# list_1.net
KiCad netlist of a schematic drawn in EAGLE
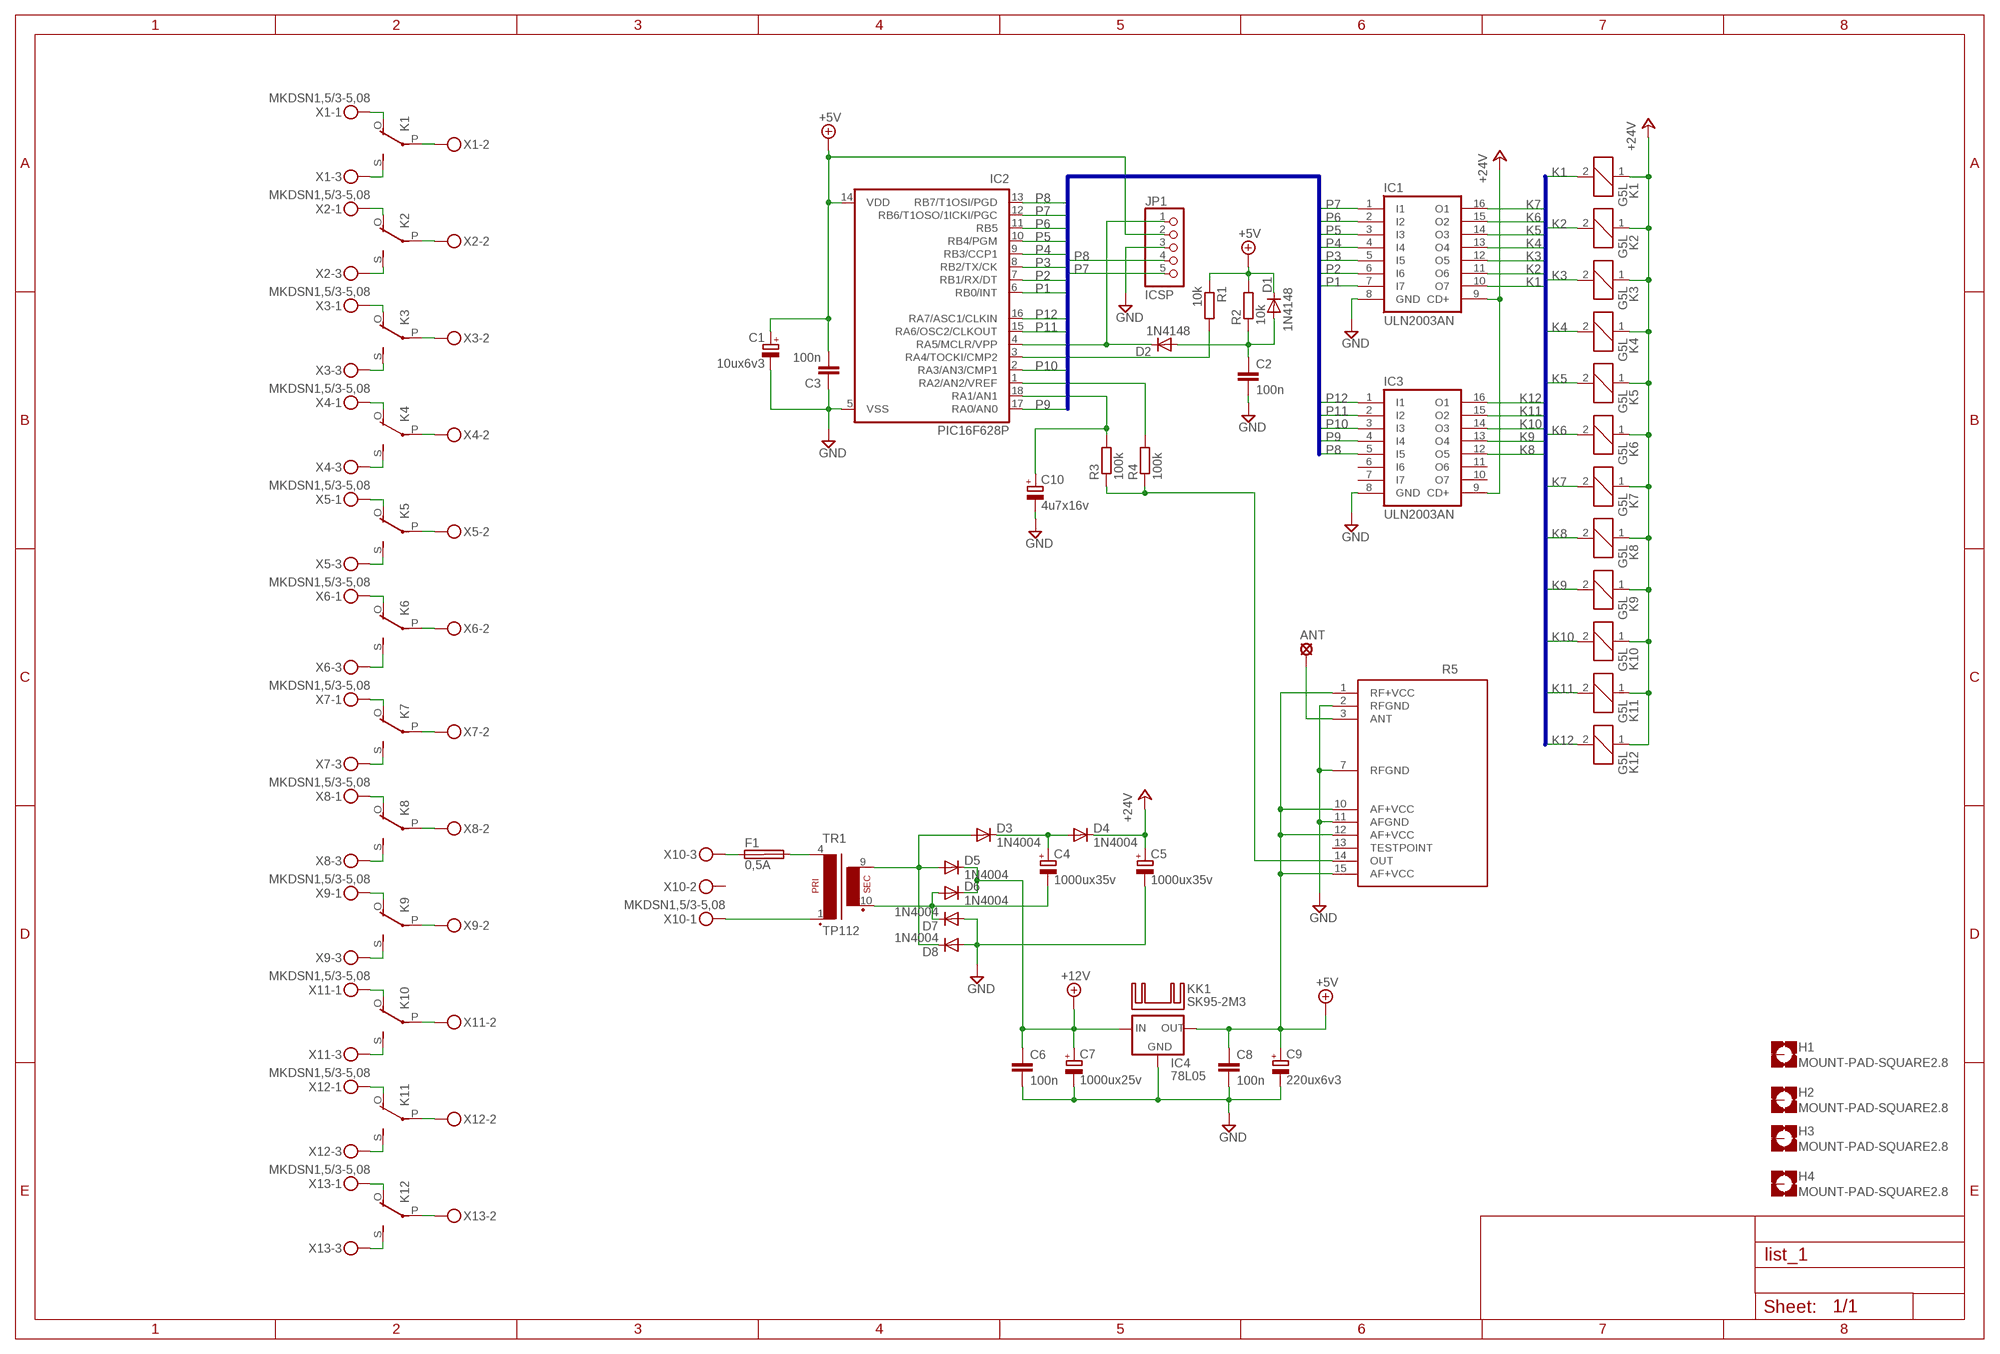
[diagram p0: schematic, sheet 1]

(export (version "E")
  (design (tool "Eeschema 10.0.6"))
  (components
    (comp (ref "ANT")
      (value "SE14")
      (footprint "eagle-import:SE14")
      (libsource (lib "eagle-import") (part "SE14"))
    )
    (comp (ref "C1")
      (value "10ux6v3")
      (footprint "eagle-import:E2,5-5")
      (libsource (lib "eagle-import") (part "CPOL-EUE2.5-5"))
    )
    (comp (ref "C2")
      (value "100n")
      (footprint "eagle-import:C050-025X075")
      (libsource (lib "eagle-import") (part "C-EU050-025X075"))
    )
    (comp (ref "C3")
      (value "100n")
      (footprint "eagle-import:C050-025X075")
      (libsource (lib "eagle-import") (part "C-EU050-025X075"))
    )
    (comp (ref "C4")
      (value "1000ux35v")
      (footprint "eagle-import:E3,5-8")
      (libsource (lib "eagle-import") (part "CPOL-EUE3.5-8"))
    )
    (comp (ref "C5")
      (value "1000ux35v")
      (footprint "eagle-import:E3,5-10")
      (libsource (lib "eagle-import") (part "CPOL-EUE3.5-10"))
    )
    (comp (ref "C6")
      (value "100n")
      (footprint "eagle-import:C050-025X075")
      (libsource (lib "eagle-import") (part "C-EU050-025X075"))
    )
    (comp (ref "C7")
      (value "1000ux25v")
      (footprint "eagle-import:E3,5-8")
      (libsource (lib "eagle-import") (part "CPOL-EUE3.5-8"))
    )
    (comp (ref "C8")
      (value "100n")
      (footprint "eagle-import:C050-025X075")
      (libsource (lib "eagle-import") (part "C-EU050-025X075"))
    )
    (comp (ref "C9")
      (value "220ux6v3")
      (footprint "eagle-import:E2,5-5")
      (libsource (lib "eagle-import") (part "CPOL-EUE2.5-5"))
    )
    (comp (ref "C10")
      (value "4u7x16v")
      (footprint "eagle-import:E2,5-5")
      (libsource (lib "eagle-import") (part "CPOL-EUE2.5-5"))
    )
    (comp (ref "D1")
      (value "1N4148")
      (footprint "eagle-import:DO35-10")
      (libsource (lib "eagle-import") (part "1N4148DO35-10"))
    )
    (comp (ref "D2")
      (value "1N4148")
      (footprint "eagle-import:DO35-10")
      (libsource (lib "eagle-import") (part "1N4148DO35-10"))
    )
    (comp (ref "D3")
      (value "1N4004")
      (footprint "eagle-import:DO41-10")
      (libsource (lib "eagle-import") (part "1N4004"))
    )
    (comp (ref "D4")
      (value "1N4004")
      (footprint "eagle-import:DO41-10")
      (libsource (lib "eagle-import") (part "1N4004"))
    )
    (comp (ref "D5")
      (value "1N4004")
      (footprint "eagle-import:DO41-10")
      (libsource (lib "eagle-import") (part "1N4004"))
    )
    (comp (ref "D6")
      (value "1N4004")
      (footprint "eagle-import:DO41-10")
      (libsource (lib "eagle-import") (part "1N4004"))
    )
    (comp (ref "D7")
      (value "1N4004")
      (footprint "eagle-import:DO41-10")
      (libsource (lib "eagle-import") (part "1N4004"))
    )
    (comp (ref "D8")
      (value "1N4004")
      (footprint "eagle-import:DO41-10")
      (libsource (lib "eagle-import") (part "1N4004"))
    )
    (comp (ref "F1")
      (value "0,5A")
      (footprint "eagle-import:SHK20L")
      (libsource (lib "eagle-import") (part "SHK20L"))
    )
    (comp (ref "H1")
      (value "MOUNT-PAD-SQUARE2.8")
      (footprint "eagle-import:2,8-PAD-SQUARE")
      (libsource (lib "eagle-import") (part "MOUNT-PAD-SQUARE2.8"))
    )
    (comp (ref "H2")
      (value "MOUNT-PAD-SQUARE2.8")
      (footprint "eagle-import:2,8-PAD-SQUARE")
      (libsource (lib "eagle-import") (part "MOUNT-PAD-SQUARE2.8"))
    )
    (comp (ref "H3")
      (value "MOUNT-PAD-SQUARE2.8")
      (footprint "eagle-import:2,8-PAD-SQUARE")
      (libsource (lib "eagle-import") (part "MOUNT-PAD-SQUARE2.8"))
    )
    (comp (ref "H4")
      (value "MOUNT-PAD-SQUARE2.8")
      (footprint "eagle-import:2,8-PAD-SQUARE")
      (libsource (lib "eagle-import") (part "MOUNT-PAD-SQUARE2.8"))
    )
    (comp (ref "IC1")
      (value "ULN2003AN")
      (footprint "eagle-import:DIL16")
      (libsource (lib "eagle-import") (part "ULN2003AN"))
    )
    (comp (ref "IC2")
      (value "PIC16F628P")
      (footprint "eagle-import:DIL18")
      (libsource (lib "eagle-import") (part "PIC16F628P"))
    )
    (comp (ref "IC3")
      (value "ULN2003AN")
      (footprint "eagle-import:DIL16")
      (libsource (lib "eagle-import") (part "ULN2003AN"))
    )
    (comp (ref "IC4")
      (value "78L05")
      (footprint "eagle-import:78XXS")
      (libsource (lib "eagle-import") (part "78XXS"))
    )
    (comp (ref "JP1")
      (value "ICSP")
      (footprint "eagle-import:1X05")
      (libsource (lib "eagle-import") (part "PINHD-1X5"))
    )
    (comp (ref "K1")
      (value "G5L")
      (footprint "eagle-import:G5LE")
      (libsource (lib "eagle-import") (part "G5L"))
    )
    (comp (ref "K2")
      (value "G5L")
      (footprint "eagle-import:G5LE")
      (libsource (lib "eagle-import") (part "G5L"))
    )
    (comp (ref "K3")
      (value "G5L")
      (footprint "eagle-import:G5LE")
      (libsource (lib "eagle-import") (part "G5L"))
    )
    (comp (ref "K4")
      (value "G5L")
      (footprint "eagle-import:G5LE")
      (libsource (lib "eagle-import") (part "G5L"))
    )
    (comp (ref "K5")
      (value "G5L")
      (footprint "eagle-import:G5LE")
      (libsource (lib "eagle-import") (part "G5L"))
    )
    (comp (ref "K6")
      (value "G5L")
      (footprint "eagle-import:G5LE")
      (libsource (lib "eagle-import") (part "G5L"))
    )
    (comp (ref "K7")
      (value "G5L")
      (footprint "eagle-import:G5LE")
      (libsource (lib "eagle-import") (part "G5L"))
    )
    (comp (ref "K8")
      (value "G5L")
      (footprint "eagle-import:G5LE")
      (libsource (lib "eagle-import") (part "G5L"))
    )
    (comp (ref "K9")
      (value "G5L")
      (footprint "eagle-import:G5LE")
      (libsource (lib "eagle-import") (part "G5L"))
    )
    (comp (ref "K10")
      (value "G5L")
      (footprint "eagle-import:G5LE")
      (libsource (lib "eagle-import") (part "G5L"))
    )
    (comp (ref "K11")
      (value "G5L")
      (footprint "eagle-import:G5LE")
      (libsource (lib "eagle-import") (part "G5L"))
    )
    (comp (ref "K12")
      (value "G5L")
      (footprint "eagle-import:G5LE")
      (libsource (lib "eagle-import") (part "G5L"))
    )
    (comp (ref "KK1")
      (value "SK95-2M3")
      (footprint "eagle-import:SK95-2M3")
      (libsource (lib "eagle-import") (part "SK95-2M3"))
    )
    (comp (ref "R1")
      (value "10k")
      (footprint "eagle-import:0207_10")
      (libsource (lib "eagle-import") (part "R-EU_0207/10"))
    )
    (comp (ref "R2")
      (value "10k")
      (footprint "eagle-import:0207_10")
      (libsource (lib "eagle-import") (part "R-EU_0207/10"))
    )
    (comp (ref "R3")
      (value "100k")
      (footprint "eagle-import:0207_10")
      (libsource (lib "eagle-import") (part "R-EU_0207/10"))
    )
    (comp (ref "R4")
      (value "100k")
      (footprint "eagle-import:0207_10")
      (libsource (lib "eagle-import") (part "R-EU_0207/10"))
    )
    (comp (ref "R5")
      (value "RR10")
      (footprint "eagle-import:RR10V")
      (libsource (lib "eagle-import") (part "RR10"))
    )
    (comp (ref "TR1")
      (value "TP112")
      (footprint "eagle-import:TR112")
      (libsource (lib "eagle-import") (part "TP112"))
    )
    (comp (ref "X1")
      (value "MKDSN1,5/3-5,08")
      (footprint "eagle-import:MKDSN1,5_3-5,08")
      (libsource (lib "eagle-import") (part "MKDSN1,5/3-5,08"))
    )
    (comp (ref "X2")
      (value "MKDSN1,5/3-5,08")
      (footprint "eagle-import:MKDSN1,5_3-5,08")
      (libsource (lib "eagle-import") (part "MKDSN1,5/3-5,08"))
    )
    (comp (ref "X3")
      (value "MKDSN1,5/3-5,08")
      (footprint "eagle-import:MKDSN1,5_3-5,08")
      (libsource (lib "eagle-import") (part "MKDSN1,5/3-5,08"))
    )
    (comp (ref "X4")
      (value "MKDSN1,5/3-5,08")
      (footprint "eagle-import:MKDSN1,5_3-5,08")
      (libsource (lib "eagle-import") (part "MKDSN1,5/3-5,08"))
    )
    (comp (ref "X5")
      (value "MKDSN1,5/3-5,08")
      (footprint "eagle-import:MKDSN1,5_3-5,08")
      (libsource (lib "eagle-import") (part "MKDSN1,5/3-5,08"))
    )
    (comp (ref "X6")
      (value "MKDSN1,5/3-5,08")
      (footprint "eagle-import:MKDSN1,5_3-5,08")
      (libsource (lib "eagle-import") (part "MKDSN1,5/3-5,08"))
    )
    (comp (ref "X7")
      (value "MKDSN1,5/3-5,08")
      (footprint "eagle-import:MKDSN1,5_3-5,08")
      (libsource (lib "eagle-import") (part "MKDSN1,5/3-5,08"))
    )
    (comp (ref "X8")
      (value "MKDSN1,5/3-5,08")
      (footprint "eagle-import:MKDSN1,5_3-5,08")
      (libsource (lib "eagle-import") (part "MKDSN1,5/3-5,08"))
    )
    (comp (ref "X9")
      (value "MKDSN1,5/3-5,08")
      (footprint "eagle-import:MKDSN1,5_3-5,08")
      (libsource (lib "eagle-import") (part "MKDSN1,5/3-5,08"))
    )
    (comp (ref "X10")
      (value "MKDSN1,5/3-5,08")
      (footprint "eagle-import:MKDSN1,5_3-5,08")
      (libsource (lib "eagle-import") (part "MKDSN1,5/3-5,08"))
    )
    (comp (ref "X11")
      (value "MKDSN1,5/3-5,08")
      (footprint "eagle-import:MKDSN1,5_3-5,08")
      (libsource (lib "eagle-import") (part "MKDSN1,5/3-5,08"))
    )
    (comp (ref "X12")
      (value "MKDSN1,5/3-5,08")
      (footprint "eagle-import:MKDSN1,5_3-5,08")
      (libsource (lib "eagle-import") (part "MKDSN1,5/3-5,08"))
    )
    (comp (ref "X13")
      (value "MKDSN1,5/3-5,08")
      (footprint "eagle-import:MKDSN1,5_3-5,08")
      (libsource (lib "eagle-import") (part "MKDSN1,5/3-5,08"))
    )
  )
  (nets
    (net (code "1") (name "+5V") (class "Default")
      (node (ref "C1") (pin "+") (pinfunction "+_+") (pintype "passive"))
      (node (ref "C3") (pin "2") (pinfunction "2_2") (pintype "passive"))
      (node (ref "C8") (pin "1") (pinfunction "1_1") (pintype "passive"))
      (node (ref "C9") (pin "+") (pinfunction "+_+") (pintype "passive"))
      (node (ref "D1") (pin "C") (pinfunction "C_C") (pintype "passive"))
      (node (ref "IC2") (pin "14") (pinfunction "VDD_14") (pintype "power_in"))
      (node (ref "IC4") (pin "OUT") (pinfunction "OUT_OUT") (pintype "passive"))
      (node (ref "JP1") (pin "2") (pinfunction "2_2") (pintype "passive"))
      (node (ref "R1") (pin "1") (pinfunction "1_1") (pintype "passive"))
      (node (ref "R2") (pin "2") (pinfunction "2_2") (pintype "passive"))
      (node (ref "R5") (pin "1") (pinfunction "RF+VCC_1") (pintype "bidirectional"))
      (node (ref "R5") (pin "10") (pinfunction "AF+VCC_10") (pintype "bidirectional"))
      (node (ref "R5") (pin "12") (pinfunction "AF+VCC_12") (pintype "bidirectional"))
      (node (ref "R5") (pin "15") (pinfunction "AF+VCC_15") (pintype "bidirectional"))
    )
    (net (code "2") (name "+12V") (class "Default")
      (node (ref "C6") (pin "1") (pinfunction "1_1") (pintype "passive"))
      (node (ref "C7") (pin "+") (pinfunction "+_+") (pintype "passive"))
      (node (ref "D5") (pin "C") (pinfunction "C_C") (pintype "passive"))
      (node (ref "D6") (pin "C") (pinfunction "C_C") (pintype "passive"))
      (node (ref "IC4") (pin "IN") (pinfunction "IN_IN") (pintype "input"))
    )
    (net (code "3") (name "+24V") (class "Default")
      (node (ref "C5") (pin "+") (pinfunction "+_+") (pintype "passive"))
      (node (ref "D4") (pin "C") (pinfunction "C_C") (pintype "passive"))
      (node (ref "IC1") (pin "9") (pinfunction "CD+_9") (pintype "passive"))
      (node (ref "IC3") (pin "9") (pinfunction "CD+_9") (pintype "passive"))
      (node (ref "K1") (pin "1") (pinfunction "1_1") (pintype "passive"))
      (node (ref "K10") (pin "1") (pinfunction "1_1") (pintype "passive"))
      (node (ref "K11") (pin "1") (pinfunction "1_1") (pintype "passive"))
      (node (ref "K12") (pin "1") (pinfunction "1_1") (pintype "passive"))
      (node (ref "K2") (pin "1") (pinfunction "1_1") (pintype "passive"))
      (node (ref "K3") (pin "1") (pinfunction "1_1") (pintype "passive"))
      (node (ref "K4") (pin "1") (pinfunction "1_1") (pintype "passive"))
      (node (ref "K5") (pin "1") (pinfunction "1_1") (pintype "passive"))
      (node (ref "K6") (pin "1") (pinfunction "1_1") (pintype "passive"))
      (node (ref "K7") (pin "1") (pinfunction "1_1") (pintype "passive"))
      (node (ref "K8") (pin "1") (pinfunction "1_1") (pintype "passive"))
      (node (ref "K9") (pin "1") (pinfunction "1_1") (pintype "passive"))
    )
    (net (code "4") (name "/K1") (class "Default")
      (node (ref "IC1") (pin "10") (pinfunction "O7_10") (pintype "open_collector"))
      (node (ref "K1") (pin "2") (pinfunction "2_2") (pintype "passive"))
    )
    (net (code "5") (name "/K2") (class "Default")
      (node (ref "IC1") (pin "11") (pinfunction "O6_11") (pintype "open_collector"))
      (node (ref "K2") (pin "2") (pinfunction "2_2") (pintype "passive"))
    )
    (net (code "6") (name "/K3") (class "Default")
      (node (ref "IC1") (pin "12") (pinfunction "O5_12") (pintype "open_collector"))
      (node (ref "K3") (pin "2") (pinfunction "2_2") (pintype "passive"))
    )
    (net (code "7") (name "/K4") (class "Default")
      (node (ref "IC1") (pin "13") (pinfunction "O4_13") (pintype "open_collector"))
      (node (ref "K4") (pin "2") (pinfunction "2_2") (pintype "passive"))
    )
    (net (code "8") (name "/K5") (class "Default")
      (node (ref "IC1") (pin "14") (pinfunction "O3_14") (pintype "open_collector"))
      (node (ref "K5") (pin "2") (pinfunction "2_2") (pintype "passive"))
    )
    (net (code "9") (name "/K6") (class "Default")
      (node (ref "IC1") (pin "15") (pinfunction "O2_15") (pintype "open_collector"))
      (node (ref "K6") (pin "2") (pinfunction "2_2") (pintype "passive"))
    )
    (net (code "10") (name "/K7") (class "Default")
      (node (ref "IC1") (pin "16") (pinfunction "O1_16") (pintype "open_collector"))
      (node (ref "K7") (pin "2") (pinfunction "2_2") (pintype "passive"))
    )
    (net (code "11") (name "/K8") (class "Default")
      (node (ref "IC3") (pin "12") (pinfunction "O5_12") (pintype "open_collector"))
      (node (ref "K8") (pin "2") (pinfunction "2_2") (pintype "passive"))
    )
    (net (code "12") (name "/K9") (class "Default")
      (node (ref "IC3") (pin "13") (pinfunction "O4_13") (pintype "open_collector"))
      (node (ref "K9") (pin "2") (pinfunction "2_2") (pintype "passive"))
    )
    (net (code "13") (name "/K10") (class "Default")
      (node (ref "IC3") (pin "14") (pinfunction "O3_14") (pintype "open_collector"))
      (node (ref "K10") (pin "2") (pinfunction "2_2") (pintype "passive"))
    )
    (net (code "14") (name "/K11") (class "Default")
      (node (ref "IC3") (pin "15") (pinfunction "O2_15") (pintype "open_collector"))
      (node (ref "K11") (pin "2") (pinfunction "2_2") (pintype "passive"))
    )
    (net (code "15") (name "/K12") (class "Default")
      (node (ref "IC3") (pin "16") (pinfunction "O1_16") (pintype "open_collector"))
      (node (ref "K12") (pin "2") (pinfunction "2_2") (pintype "passive"))
    )
    (net (code "16") (name "/P1") (class "Default")
      (node (ref "IC1") (pin "7") (pinfunction "I7_7") (pintype "input"))
      (node (ref "IC2") (pin "6") (pinfunction "RB0/INT_6") (pintype "bidirectional"))
    )
    (net (code "17") (name "/P2") (class "Default")
      (node (ref "IC1") (pin "6") (pinfunction "I6_6") (pintype "input"))
      (node (ref "IC2") (pin "7") (pinfunction "RB1/RX/DT_7") (pintype "bidirectional"))
    )
    (net (code "18") (name "/P3") (class "Default")
      (node (ref "IC1") (pin "5") (pinfunction "I5_5") (pintype "input"))
      (node (ref "IC2") (pin "8") (pinfunction "RB2/TX/CK_8") (pintype "bidirectional"))
    )
    (net (code "19") (name "/P4") (class "Default")
      (node (ref "IC1") (pin "4") (pinfunction "I4_4") (pintype "input"))
      (node (ref "IC2") (pin "9") (pinfunction "RB3/CCP1_9") (pintype "bidirectional"))
    )
    (net (code "20") (name "/P5") (class "Default")
      (node (ref "IC1") (pin "3") (pinfunction "I3_3") (pintype "input"))
      (node (ref "IC2") (pin "10") (pinfunction "RB4/PGM_10") (pintype "bidirectional"))
    )
    (net (code "21") (name "/P6") (class "Default")
      (node (ref "IC1") (pin "2") (pinfunction "I2_2") (pintype "input"))
      (node (ref "IC2") (pin "11") (pinfunction "RB5_11") (pintype "bidirectional"))
    )
    (net (code "22") (name "/P7") (class "Default")
      (node (ref "IC1") (pin "1") (pinfunction "I1_1") (pintype "input"))
      (node (ref "IC2") (pin "12") (pinfunction "RB6/T1OSO/1ICKI/PGC_12") (pintype "bidirectional"))
      (node (ref "JP1") (pin "5") (pinfunction "5_5") (pintype "passive"))
    )
    (net (code "23") (name "/P8") (class "Default")
      (node (ref "IC2") (pin "13") (pinfunction "RB7/T1OSI/PGD_13") (pintype "bidirectional"))
      (node (ref "IC3") (pin "5") (pinfunction "I5_5") (pintype "input"))
      (node (ref "JP1") (pin "4") (pinfunction "4_4") (pintype "passive"))
    )
    (net (code "24") (name "/P9") (class "Default")
      (node (ref "IC2") (pin "17") (pinfunction "RA0/AN0_17") (pintype "bidirectional"))
      (node (ref "IC3") (pin "4") (pinfunction "I4_4") (pintype "input"))
    )
    (net (code "25") (name "/P10") (class "Default")
      (node (ref "IC2") (pin "2") (pinfunction "RA3/AN3/CMP1_2") (pintype "bidirectional"))
      (node (ref "IC3") (pin "3") (pinfunction "I3_3") (pintype "input"))
    )
    (net (code "26") (name "/P11") (class "Default")
      (node (ref "IC2") (pin "15") (pinfunction "RA6/OSC2/CLKOUT_15") (pintype "bidirectional"))
      (node (ref "IC3") (pin "2") (pinfunction "I2_2") (pintype "input"))
    )
    (net (code "27") (name "/P12") (class "Default")
      (node (ref "IC2") (pin "16") (pinfunction "RA7/ASC1/CLKIN_16") (pintype "bidirectional"))
      (node (ref "IC3") (pin "1") (pinfunction "I1_1") (pintype "input"))
    )
    (net (code "28") (name "GND") (class "Default")
      (node (ref "C1") (pin "-") (pinfunction "-_-") (pintype "passive"))
      (node (ref "C10") (pin "-") (pinfunction "-_-") (pintype "passive"))
      (node (ref "C2") (pin "2") (pinfunction "2_2") (pintype "passive"))
      (node (ref "C3") (pin "1") (pinfunction "1_1") (pintype "passive"))
      (node (ref "C5") (pin "-") (pinfunction "-_-") (pintype "passive"))
      (node (ref "C6") (pin "2") (pinfunction "2_2") (pintype "passive"))
      (node (ref "C7") (pin "-") (pinfunction "-_-") (pintype "passive"))
      (node (ref "C8") (pin "2") (pinfunction "2_2") (pintype "passive"))
      (node (ref "C9") (pin "-") (pinfunction "-_-") (pintype "passive"))
      (node (ref "D7") (pin "A") (pinfunction "A_A") (pintype "passive"))
      (node (ref "D8") (pin "A") (pinfunction "A_A") (pintype "passive"))
      (node (ref "IC1") (pin "8") (pinfunction "GND_8") (pintype "power_in"))
      (node (ref "IC2") (pin "5") (pinfunction "VSS_5") (pintype "power_in"))
      (node (ref "IC3") (pin "8") (pinfunction "GND_8") (pintype "power_in"))
      (node (ref "IC4") (pin "GND") (pinfunction "GND_GND") (pintype "input"))
      (node (ref "JP1") (pin "3") (pinfunction "3_3") (pintype "passive"))
      (node (ref "R5") (pin "11") (pinfunction "AFGND_11") (pintype "bidirectional"))
      (node (ref "R5") (pin "2") (pinfunction "RFGND_2") (pintype "bidirectional"))
      (node (ref "R5") (pin "7") (pinfunction "RFGND_7") (pintype "bidirectional"))
    )
    (net (code "29") (name "Net-(C2-Pad1)") (class "Default")
      (node (ref "C2") (pin "1") (pinfunction "1_1") (pintype "passive"))
      (node (ref "D1") (pin "A") (pinfunction "A_A") (pintype "passive"))
      (node (ref "D2") (pin "A") (pinfunction "A_A") (pintype "passive"))
      (node (ref "R2") (pin "1") (pinfunction "1_1") (pintype "passive"))
    )
    (net (code "30") (name "Net-(C4-Pad+)") (class "Default")
      (node (ref "C4") (pin "+") (pinfunction "+_+") (pintype "passive"))
      (node (ref "D3") (pin "C") (pinfunction "C_C") (pintype "passive"))
      (node (ref "D4") (pin "A") (pinfunction "A_A") (pintype "passive"))
    )
    (net (code "31") (name "Net-(IC2-RA1{slash}AN1)") (class "Default")
      (node (ref "C10") (pin "+") (pinfunction "+_+") (pintype "passive"))
      (node (ref "IC2") (pin "18") (pinfunction "RA1/AN1_18") (pintype "bidirectional"))
      (node (ref "R3") (pin "2") (pinfunction "2_2") (pintype "passive"))
    )
    (net (code "32") (name "Net-(IC2-RA2{slash}AN2{slash}VREF)") (class "Default")
      (node (ref "IC2") (pin "1") (pinfunction "RA2/AN2/VREF_1") (pintype "bidirectional"))
      (node (ref "R4") (pin "2") (pinfunction "2_2") (pintype "passive"))
    )
    (net (code "33") (name "Net-(IC2-RA4{slash}TOCKI{slash}CMP2)") (class "Default")
      (node (ref "IC2") (pin "3") (pinfunction "RA4/TOCKI/CMP2_3") (pintype "bidirectional"))
      (node (ref "R1") (pin "2") (pinfunction "2_2") (pintype "passive"))
    )
    (net (code "34") (name "Net-(IC2-RA5{slash}MCLR{slash}VPP)") (class "Default")
      (node (ref "D2") (pin "C") (pinfunction "C_C") (pintype "passive"))
      (node (ref "IC2") (pin "4") (pinfunction "RA5/MCLR/VPP_4") (pintype "input"))
      (node (ref "JP1") (pin "1") (pinfunction "1_1") (pintype "passive"))
    )
    (net (code "35") (name "Net-(R5-ANT)") (class "Default")
      (node (ref "ANT") (pin "MP") (pinfunction "MP_MP") (pintype "passive"))
      (node (ref "R5") (pin "3") (pinfunction "ANT_3") (pintype "bidirectional"))
    )
    (net (code "36") (name "Net-(R5-OUT)") (class "Default")
      (node (ref "R3") (pin "1") (pinfunction "1_1") (pintype "passive"))
      (node (ref "R4") (pin "1") (pinfunction "1_1") (pintype "passive"))
      (node (ref "R5") (pin "14") (pinfunction "OUT_14") (pintype "bidirectional"))
    )
    (net (code "37") (name "Net-(TR1-P1)") (class "Default")
      (node (ref "F1") (pin "2A") (pinfunction "2A_2A") (pintype "passive"))
      (node (ref "TR1") (pin "4") (pinfunction "P1_4") (pintype "passive"))
    )
    (net (code "38") (name "Net-(TR1-P2)") (class "Default")
      (node (ref "TR1") (pin "1") (pinfunction "P2_1") (pintype "passive"))
      (node (ref "X10") (pin "1") (pinfunction "KL_1") (pintype "passive"))
    )
    (net (code "39") (name "Net-(TR1-S3)") (class "Default")
      (node (ref "C4") (pin "-") (pinfunction "-_-") (pintype "passive"))
      (node (ref "D6") (pin "A") (pinfunction "A_A") (pintype "passive"))
      (node (ref "D7") (pin "C") (pinfunction "C_C") (pintype "passive"))
      (node (ref "TR1") (pin "10") (pinfunction "S3_10") (pintype "passive"))
    )
    (net (code "40") (name "Net-(TR1-S4)") (class "Default")
      (node (ref "D3") (pin "A") (pinfunction "A_A") (pintype "passive"))
      (node (ref "D5") (pin "A") (pinfunction "A_A") (pintype "passive"))
      (node (ref "D8") (pin "C") (pinfunction "C_C") (pintype "passive"))
      (node (ref "TR1") (pin "9") (pinfunction "S4_9") (pintype "passive"))
    )
    (net (code "41") (name "Net-(X1A-KL)") (class "Default")
      (node (ref "K1") (pin "O") (pinfunction "O_O") (pintype "passive"))
      (node (ref "X1") (pin "1") (pinfunction "KL_1") (pintype "passive"))
    )
    (net (code "42") (name "Net-(X1B-KL)") (class "Default")
      (node (ref "K1") (pin "P") (pinfunction "P_P") (pintype "passive"))
      (node (ref "X1") (pin "2") (pinfunction "KL_2") (pintype "passive"))
    )
    (net (code "43") (name "Net-(X1C-KL)") (class "Default")
      (node (ref "K1") (pin "S") (pinfunction "S_S") (pintype "passive"))
      (node (ref "X1") (pin "3") (pinfunction "KL_3") (pintype "passive"))
    )
    (net (code "44") (name "Net-(X2A-KL)") (class "Default")
      (node (ref "K2") (pin "O") (pinfunction "O_O") (pintype "passive"))
      (node (ref "X2") (pin "1") (pinfunction "KL_1") (pintype "passive"))
    )
    (net (code "45") (name "Net-(X2B-KL)") (class "Default")
      (node (ref "K2") (pin "P") (pinfunction "P_P") (pintype "passive"))
      (node (ref "X2") (pin "2") (pinfunction "KL_2") (pintype "passive"))
    )
    (net (code "46") (name "Net-(X2C-KL)") (class "Default")
      (node (ref "K2") (pin "S") (pinfunction "S_S") (pintype "passive"))
      (node (ref "X2") (pin "3") (pinfunction "KL_3") (pintype "passive"))
    )
    (net (code "47") (name "Net-(X3A-KL)") (class "Default")
      (node (ref "K3") (pin "O") (pinfunction "O_O") (pintype "passive"))
      (node (ref "X3") (pin "1") (pinfunction "KL_1") (pintype "passive"))
    )
    (net (code "48") (name "Net-(X3B-KL)") (class "Default")
      (node (ref "K3") (pin "P") (pinfunction "P_P") (pintype "passive"))
      (node (ref "X3") (pin "2") (pinfunction "KL_2") (pintype "passive"))
    )
    (net (code "49") (name "Net-(X3C-KL)") (class "Default")
      (node (ref "K3") (pin "S") (pinfunction "S_S") (pintype "passive"))
      (node (ref "X3") (pin "3") (pinfunction "KL_3") (pintype "passive"))
    )
    (net (code "50") (name "Net-(X4A-KL)") (class "Default")
      (node (ref "K4") (pin "O") (pinfunction "O_O") (pintype "passive"))
      (node (ref "X4") (pin "1") (pinfunction "KL_1") (pintype "passive"))
    )
    (net (code "51") (name "Net-(X4B-KL)") (class "Default")
      (node (ref "K4") (pin "P") (pinfunction "P_P") (pintype "passive"))
      (node (ref "X4") (pin "2") (pinfunction "KL_2") (pintype "passive"))
    )
    (net (code "52") (name "Net-(X4C-KL)") (class "Default")
      (node (ref "K4") (pin "S") (pinfunction "S_S") (pintype "passive"))
      (node (ref "X4") (pin "3") (pinfunction "KL_3") (pintype "passive"))
    )
    (net (code "53") (name "Net-(X5A-KL)") (class "Default")
      (node (ref "K5") (pin "O") (pinfunction "O_O") (pintype "passive"))
      (node (ref "X5") (pin "1") (pinfunction "KL_1") (pintype "passive"))
    )
    (net (code "54") (name "Net-(X5B-KL)") (class "Default")
      (node (ref "K5") (pin "P") (pinfunction "P_P") (pintype "passive"))
      (node (ref "X5") (pin "2") (pinfunction "KL_2") (pintype "passive"))
    )
    (net (code "55") (name "Net-(X5C-KL)") (class "Default")
      (node (ref "K5") (pin "S") (pinfunction "S_S") (pintype "passive"))
      (node (ref "X5") (pin "3") (pinfunction "KL_3") (pintype "passive"))
    )
    (net (code "56") (name "Net-(X6A-KL)") (class "Default")
      (node (ref "K6") (pin "O") (pinfunction "O_O") (pintype "passive"))
      (node (ref "X6") (pin "1") (pinfunction "KL_1") (pintype "passive"))
    )
    (net (code "57") (name "Net-(X6B-KL)") (class "Default")
      (node (ref "K6") (pin "P") (pinfunction "P_P") (pintype "passive"))
      (node (ref "X6") (pin "2") (pinfunction "KL_2") (pintype "passive"))
    )
    (net (code "58") (name "Net-(X6C-KL)") (class "Default")
      (node (ref "K6") (pin "S") (pinfunction "S_S") (pintype "passive"))
      (node (ref "X6") (pin "3") (pinfunction "KL_3") (pintype "passive"))
    )
    (net (code "59") (name "Net-(X7A-KL)") (class "Default")
      (node (ref "K7") (pin "O") (pinfunction "O_O") (pintype "passive"))
      (node (ref "X7") (pin "1") (pinfunction "KL_1") (pintype "passive"))
    )
    (net (code "60") (name "Net-(X7B-KL)") (class "Default")
      (node (ref "K7") (pin "P") (pinfunction "P_P") (pintype "passive"))
      (node (ref "X7") (pin "2") (pinfunction "KL_2") (pintype "passive"))
    )
    (net (code "61") (name "Net-(X7C-KL)") (class "Default")
      (node (ref "K7") (pin "S") (pinfunction "S_S") (pintype "passive"))
      (node (ref "X7") (pin "3") (pinfunction "KL_3") (pintype "passive"))
    )
    (net (code "62") (name "Net-(X8A-KL)") (class "Default")
      (node (ref "K8") (pin "O") (pinfunction "O_O") (pintype "passive"))
      (node (ref "X8") (pin "1") (pinfunction "KL_1") (pintype "passive"))
    )
    (net (code "63") (name "Net-(X8B-KL)") (class "Default")
      (node (ref "K8") (pin "P") (pinfunction "P_P") (pintype "passive"))
      (node (ref "X8") (pin "2") (pinfunction "KL_2") (pintype "passive"))
    )
    (net (code "64") (name "Net-(X8C-KL)") (class "Default")
      (node (ref "K8") (pin "S") (pinfunction "S_S") (pintype "passive"))
      (node (ref "X8") (pin "3") (pinfunction "KL_3") (pintype "passive"))
    )
    (net (code "65") (name "Net-(X9A-KL)") (class "Default")
      (node (ref "K9") (pin "O") (pinfunction "O_O") (pintype "passive"))
      (node (ref "X9") (pin "1") (pinfunction "KL_1") (pintype "passive"))
    )
    (net (code "66") (name "Net-(X9B-KL)") (class "Default")
      (node (ref "K9") (pin "P") (pinfunction "P_P") (pintype "passive"))
      (node (ref "X9") (pin "2") (pinfunction "KL_2") (pintype "passive"))
    )
    (net (code "67") (name "Net-(X9C-KL)") (class "Default")
      (node (ref "K9") (pin "S") (pinfunction "S_S") (pintype "passive"))
      (node (ref "X9") (pin "3") (pinfunction "KL_3") (pintype "passive"))
    )
    (net (code "68") (name "Net-(X10C-KL)") (class "Default")
      (node (ref "F1") (pin "1A") (pinfunction "1A_1A") (pintype "passive"))
      (node (ref "X10") (pin "3") (pinfunction "KL_3") (pintype "passive"))
    )
    (net (code "69") (name "Net-(X11A-KL)") (class "Default")
      (node (ref "K10") (pin "O") (pinfunction "O_O") (pintype "passive"))
      (node (ref "X11") (pin "1") (pinfunction "KL_1") (pintype "passive"))
    )
    (net (code "70") (name "Net-(X11B-KL)") (class "Default")
      (node (ref "K10") (pin "P") (pinfunction "P_P") (pintype "passive"))
      (node (ref "X11") (pin "2") (pinfunction "KL_2") (pintype "passive"))
    )
    (net (code "71") (name "Net-(X11C-KL)") (class "Default")
      (node (ref "K10") (pin "S") (pinfunction "S_S") (pintype "passive"))
      (node (ref "X11") (pin "3") (pinfunction "KL_3") (pintype "passive"))
    )
    (net (code "72") (name "Net-(X12A-KL)") (class "Default")
      (node (ref "K11") (pin "O") (pinfunction "O_O") (pintype "passive"))
      (node (ref "X12") (pin "1") (pinfunction "KL_1") (pintype "passive"))
    )
    (net (code "73") (name "Net-(X12B-KL)") (class "Default")
      (node (ref "K11") (pin "P") (pinfunction "P_P") (pintype "passive"))
      (node (ref "X12") (pin "2") (pinfunction "KL_2") (pintype "passive"))
    )
    (net (code "74") (name "Net-(X12C-KL)") (class "Default")
      (node (ref "K11") (pin "S") (pinfunction "S_S") (pintype "passive"))
      (node (ref "X12") (pin "3") (pinfunction "KL_3") (pintype "passive"))
    )
    (net (code "75") (name "Net-(X13A-KL)") (class "Default")
      (node (ref "K12") (pin "O") (pinfunction "O_O") (pintype "passive"))
      (node (ref "X13") (pin "1") (pinfunction "KL_1") (pintype "passive"))
    )
    (net (code "76") (name "Net-(X13B-KL)") (class "Default")
      (node (ref "K12") (pin "P") (pinfunction "P_P") (pintype "passive"))
      (node (ref "X13") (pin "2") (pinfunction "KL_2") (pintype "passive"))
    )
    (net (code "77") (name "Net-(X13C-KL)") (class "Default")
      (node (ref "K12") (pin "S") (pinfunction "S_S") (pintype "passive"))
      (node (ref "X13") (pin "3") (pinfunction "KL_3") (pintype "passive"))
    )
    (net (code "78") (name "unconnected-(F1-Pad1B)") (class "Default")
      (node (ref "F1") (pin "1B") (pinfunction "1B_1B") (pintype "passive"))
    )
    (net (code "79") (name "unconnected-(F1-Pad2B)") (class "Default")
      (node (ref "F1") (pin "2B") (pinfunction "2B_2B") (pintype "passive"))
    )
    (net (code "80") (name "unconnected-(H1-MOUNT-PadB2,8)") (class "Default")
      (node (ref "H1") (pin "B2,8") (pinfunction "MOUNT_B2,8") (pintype "passive"))
    )
    (net (code "81") (name "unconnected-(H2-MOUNT-PadB2,8)") (class "Default")
      (node (ref "H2") (pin "B2,8") (pinfunction "MOUNT_B2,8") (pintype "passive"))
    )
    (net (code "82") (name "unconnected-(H3-MOUNT-PadB2,8)") (class "Default")
      (node (ref "H3") (pin "B2,8") (pinfunction "MOUNT_B2,8") (pintype "passive"))
    )
    (net (code "83") (name "unconnected-(H4-MOUNT-PadB2,8)") (class "Default")
      (node (ref "H4") (pin "B2,8") (pinfunction "MOUNT_B2,8") (pintype "passive"))
    )
    (net (code "84") (name "unconnected-(IC3-I6-Pad6)") (class "Default")
      (node (ref "IC3") (pin "6") (pinfunction "I6_6") (pintype "input"))
    )
    (net (code "85") (name "unconnected-(IC3-I7-Pad7)") (class "Default")
      (node (ref "IC3") (pin "7") (pinfunction "I7_7") (pintype "input"))
    )
    (net (code "86") (name "unconnected-(IC3-O6-Pad11)") (class "Default")
      (node (ref "IC3") (pin "11") (pinfunction "O6_11") (pintype "open_collector"))
    )
    (net (code "87") (name "unconnected-(IC3-O7-Pad10)") (class "Default")
      (node (ref "IC3") (pin "10") (pinfunction "O7_10") (pintype "open_collector"))
    )
    (net (code "88") (name "unconnected-(R5-TESTPOINT-Pad13)") (class "Default")
      (node (ref "R5") (pin "13") (pinfunction "TESTPOINT_13") (pintype "bidirectional"))
    )
    (net (code "89") (name "unconnected-(X10B-KL-Pad2)") (class "Default")
      (node (ref "X10") (pin "2") (pinfunction "KL_2") (pintype "passive"))
    )
  )
)
